# Drive_Board_Schematic_3_motors.net
KiCad netlist of a schematic drawn in Altium Designer
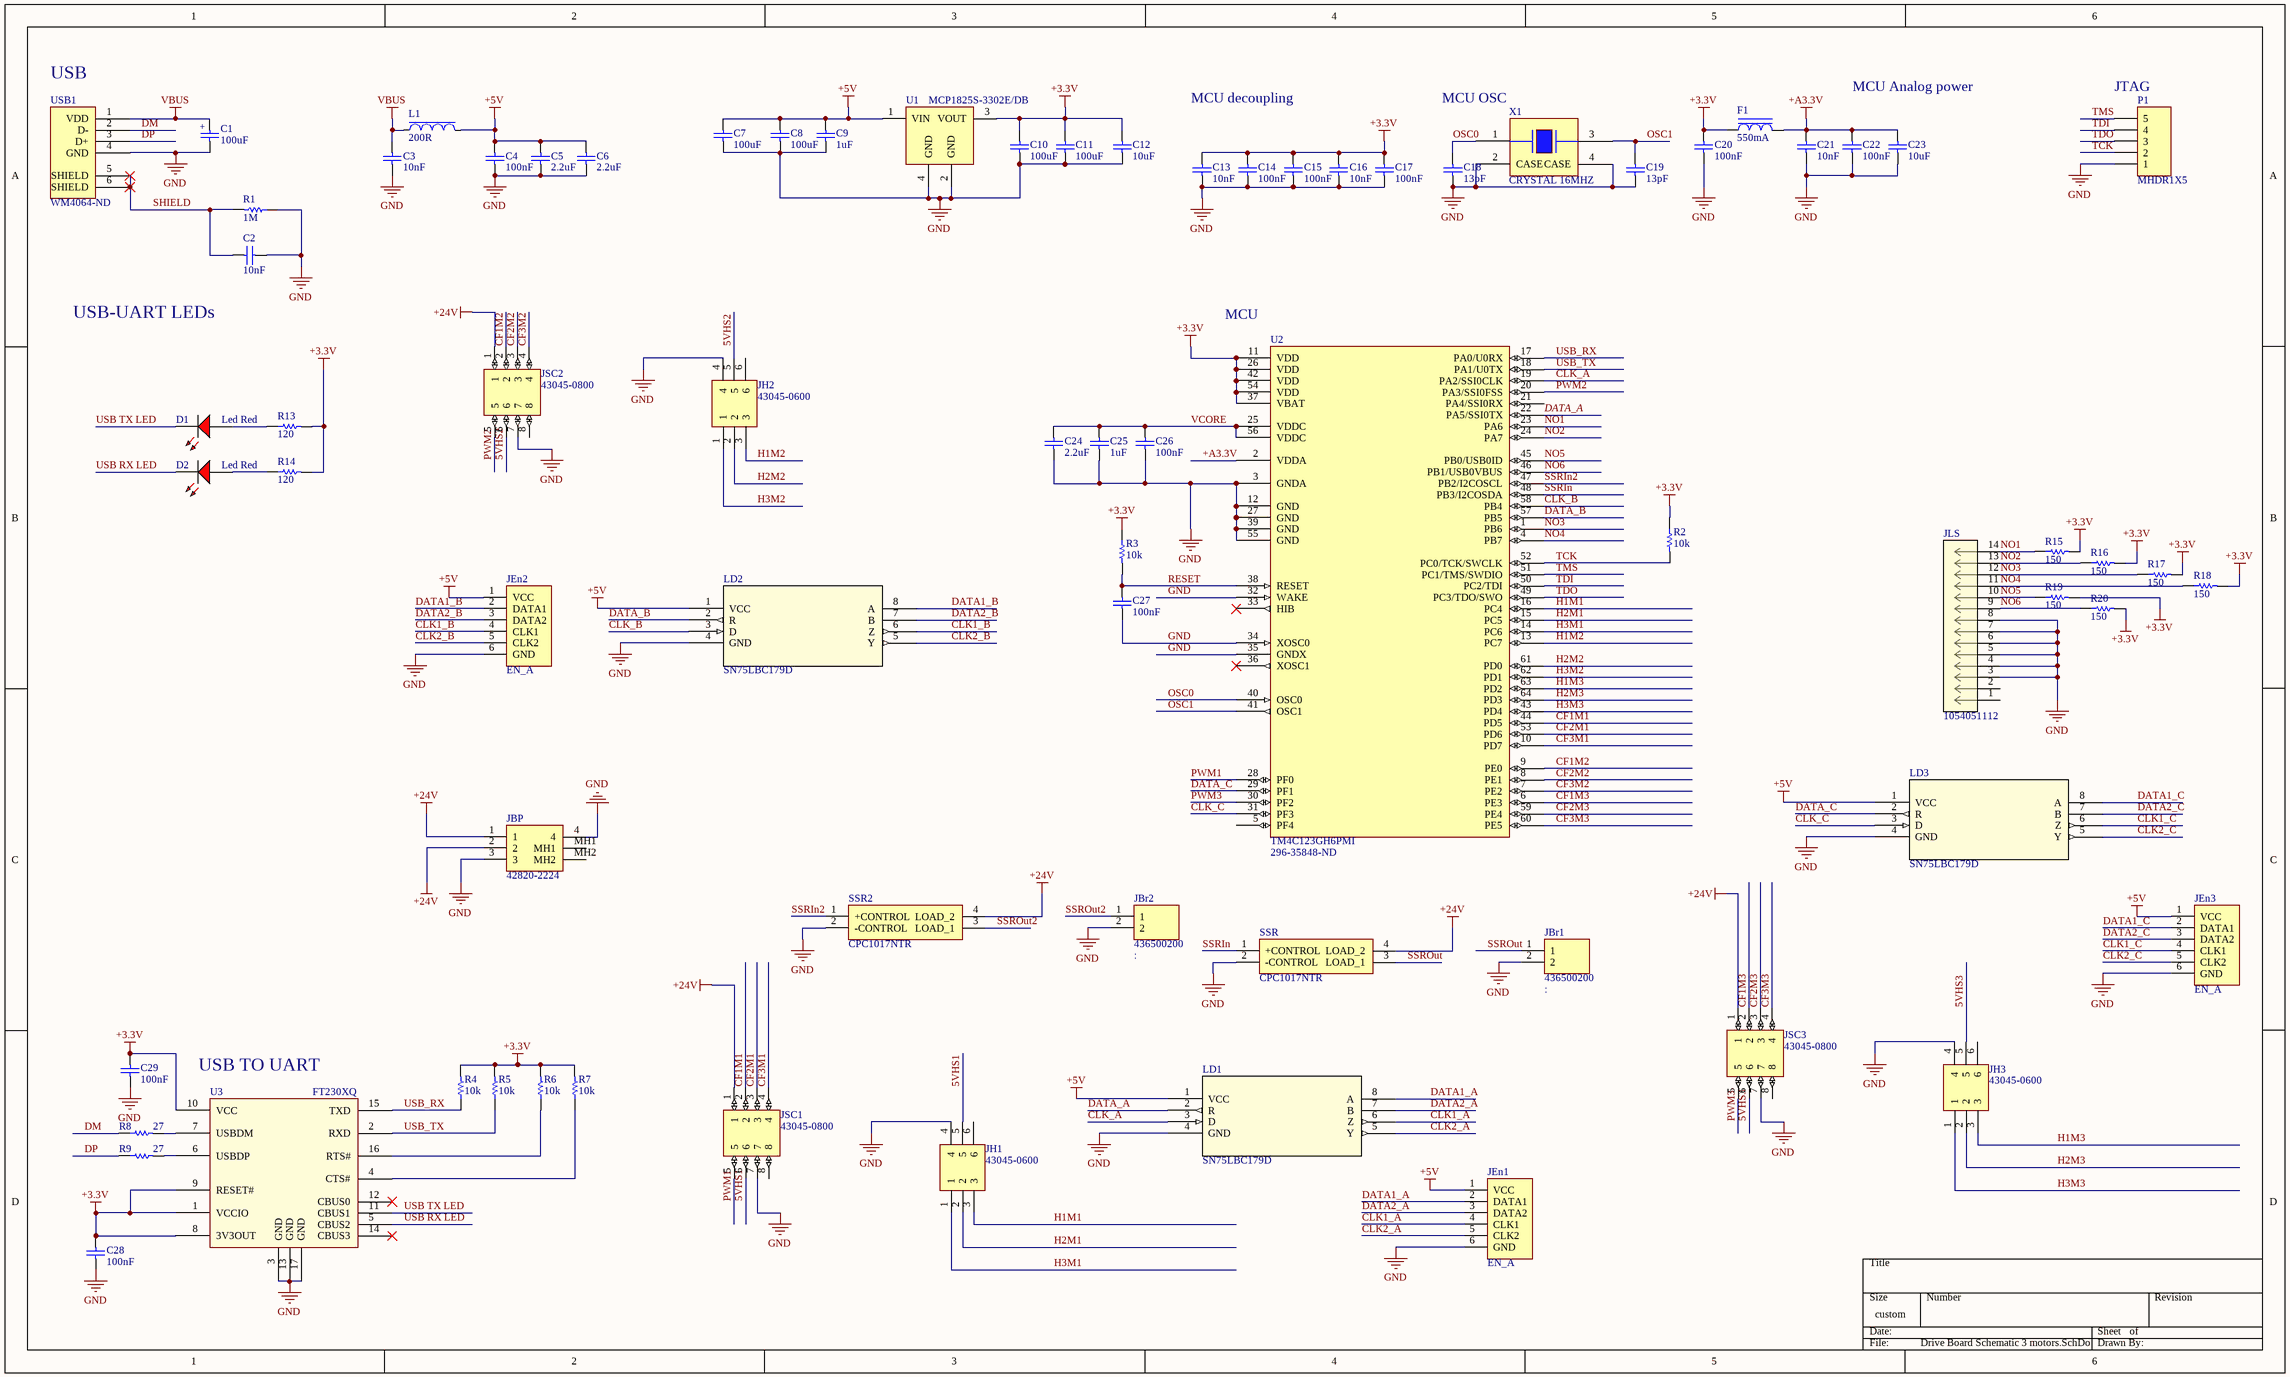
[diagram p0: Drive Board Schematic 3 motors.SchDoc]

(export (version "E")
  (design (tool "Eeschema 10.0.6"))
  (components
    (comp (ref "C1")
      (value "100uF")
      (footprint "CapAlu6.3mmx12.5mm")
      (description "Capacitor 35v 100uF 6.3mm")
      (fields
        (field (name "MANUFACTURER") "Nichicon")
        (field (name "MANUFACTURER PART NUMBER") "UHV1V101MED")
      )
      (libsource (lib "Capacitors") (part "100uF_35v_6.3x12.5"))
    )
    (comp (ref "C2")
      (value "10nF")
      (footprint "CAP_1206")
      (description "CAP CER 10000PF 500V X7R 1206")
      (fields
        (field (name "MANUFACTURER") "Samsung Electro-Mechanics America, Inc")
        (field (name "MANUFACTURER PART NUMBER") "CL31B103KGFNNNE")
      )
      (libsource (lib "Capacitors") (part "10nF_500V_1206"))
    )
    (comp (ref "C3")
      (value "10nF")
      (footprint "CAP_0402_M")
      (description "CAP CER 10000PF 50V 10% X7R 0402")
      (fields
        (field (name "MANUFACTURER") "Kemet")
        (field (name "MANUFACTURER PART NUMBER") "C0402C103K5RACTU")
      )
      (libsource (lib "Capacitors") (part "10nF_50V_0402"))
    )
    (comp (ref "C4")
      (value "100nF")
      (footprint "CAP_0402_M")
      (description "CAP CER 100NF 50V 20% X5R 0402")
      (fields
        (field (name "MANUFACTURER") "TDK Corporation")
        (field (name "MANUFACTURER PART NUMBER") "C1005X5R1H104M050BB")
      )
      (libsource (lib "Capacitors") (part "100nF_50V_0402"))
    )
    (comp (ref "C5")
      (value "2.2uF")
      (footprint "CAP_0402_M")
      (description "CAP CER 2.2UF 10V 20% X5R 0402")
      (fields
        (field (name "MANUFACTURER") "Taiyo Yuden")
        (field (name "MANUFACTURER PART NUMBER") "LMK105BJ225MV-F")
      )
      (libsource (lib "Capacitors") (part "2.2uF_10V_0402"))
    )
    (comp (ref "C6")
      (value "2.2uF")
      (footprint "CAP_0402_M")
      (description "CAP CER 2.2UF 10V 20% X5R 0402")
      (fields
        (field (name "MANUFACTURER") "Taiyo Yuden")
        (field (name "MANUFACTURER PART NUMBER") "LMK105BJ225MV-F")
      )
      (libsource (lib "Capacitors") (part "2.2uF_10V_0402"))
    )
    (comp (ref "C7")
      (value "100uF")
      (footprint "CAP_1206")
      (description "CAP CER 100UF 6.3V X5R 1206")
      (fields
        (field (name "MANUFACTURER") "Murata Electronics North America")
        (field (name "MANUFACTURER PART NUMBER") "GRM31CR60J107ME39L")
      )
      (libsource (lib "Capacitors") (part "100uF_6.3v_1206_X5R"))
    )
    (comp (ref "C8")
      (value "100uF")
      (footprint "CAP_1206")
      (description "CAP CER 100UF 6.3V X5R 1206")
      (fields
        (field (name "MANUFACTURER") "Murata Electronics North America")
        (field (name "MANUFACTURER PART NUMBER") "GRM31CR60J107ME39L")
      )
      (libsource (lib "Capacitors") (part "100uF_6.3v_1206_X5R"))
    )
    (comp (ref "C9")
      (value "1uF")
      (footprint "CAP_0402_M")
      (description "CAP CER 1UF 25V 10% X5R 0402")
      (fields
        (field (name "MANUFACTURER") "TDK Corporation")
        (field (name "MANUFACTURER PART NUMBER") "C1005X5R1E105K050BC")
      )
      (libsource (lib "Capacitors") (part "1uF_25V_0402"))
    )
    (comp (ref "C10")
      (value "100uF")
      (footprint "CAP_1206")
      (description "CAP CER 100UF 6.3V X5R 1206")
      (fields
        (field (name "MANUFACTURER") "Murata Electronics North America")
        (field (name "MANUFACTURER PART NUMBER") "GRM31CR60J107ME39L")
      )
      (libsource (lib "Capacitors") (part "100uF_6.3v_1206_X5R"))
    )
    (comp (ref "C11")
      (value "100uF")
      (footprint "CAP_1206")
      (description "CAP CER 100UF 6.3V X5R 1206")
      (fields
        (field (name "MANUFACTURER") "Murata Electronics North America")
        (field (name "MANUFACTURER PART NUMBER") "GRM31CR60J107ME39L")
      )
      (libsource (lib "Capacitors") (part "100uF_6.3v_1206_X5R"))
    )
    (comp (ref "C12")
      (value "10uF")
      (footprint "CAP_0603")
      (description "CAP CER 10UF 10V 20% X5R 0603")
      (fields
        (field (name "MANUFACTURER") "Taiyo Yuden")
        (field (name "MANUFACTURER PART NUMBER") "LMK107BBJ106MAHT")
      )
      (libsource (lib "Capacitors") (part "10uF_10V_0603"))
    )
    (comp (ref "C13")
      (value "10nF")
      (footprint "CAP_0402_M")
      (description "CAP CER 10000PF 50V 10% X7R 0402")
      (fields
        (field (name "MANUFACTURER") "Kemet")
        (field (name "MANUFACTURER PART NUMBER") "C0402C103K5RACTU")
      )
      (libsource (lib "Capacitors") (part "10nF_50V_0402"))
    )
    (comp (ref "C14")
      (value "100nF")
      (footprint "CAP_0402_M")
      (description "CAP CER 100NF 50V 20% X5R 0402")
      (fields
        (field (name "MANUFACTURER") "TDK Corporation")
        (field (name "MANUFACTURER PART NUMBER") "C1005X5R1H104M050BB")
      )
      (libsource (lib "Capacitors") (part "100nF_50V_0402"))
    )
    (comp (ref "C15")
      (value "100nF")
      (footprint "CAP_0402_M")
      (description "CAP CER 100NF 50V 20% X5R 0402")
      (fields
        (field (name "MANUFACTURER") "TDK Corporation")
        (field (name "MANUFACTURER PART NUMBER") "C1005X5R1H104M050BB")
      )
      (libsource (lib "Capacitors") (part "100nF_50V_0402"))
    )
    (comp (ref "C16")
      (value "10nF")
      (footprint "CAP_0402_M")
      (description "CAP CER 10000PF 50V 10% X7R 0402")
      (fields
        (field (name "MANUFACTURER") "Kemet")
        (field (name "MANUFACTURER PART NUMBER") "C0402C103K5RACTU")
      )
      (libsource (lib "Capacitors") (part "10nF_50V_0402"))
    )
    (comp (ref "C17")
      (value "100nF")
      (footprint "CAP_0402_M")
      (description "CAP CER 100NF 50V 20% X5R 0402")
      (fields
        (field (name "MANUFACTURER") "TDK Corporation")
        (field (name "MANUFACTURER PART NUMBER") "C1005X5R1H104M050BB")
      )
      (libsource (lib "Capacitors") (part "100nF_50V_0402"))
    )
    (comp (ref "C18")
      (value "13pF")
      (footprint "CAP_0402_M")
      (description "CAP CER 13PF 50V 5% NP0 0402")
      (fields
        (field (name "MANUFACTURER") "Samsung Electro-Mechanics America, Inc")
        (field (name "MANUFACTURER PART NUMBER") "CL05C130JB5NNNC")
      )
      (libsource (lib "Capacitors") (part "13pF_50V_0402"))
    )
    (comp (ref "C19")
      (value "13pF")
      (footprint "CAP_0402_M")
      (description "CAP CER 13PF 50V 5% NP0 0402")
      (fields
        (field (name "MANUFACTURER") "Samsung Electro-Mechanics America, Inc")
        (field (name "MANUFACTURER PART NUMBER") "CL05C130JB5NNNC")
      )
      (libsource (lib "Capacitors") (part "13pF_50V_0402"))
    )
    (comp (ref "C20")
      (value "100nF")
      (footprint "CAP_0402_M")
      (description "CAP CER 100NF 50V 20% X5R 0402")
      (fields
        (field (name "MANUFACTURER") "TDK Corporation")
        (field (name "MANUFACTURER PART NUMBER") "C1005X5R1H104M050BB")
      )
      (libsource (lib "Capacitors") (part "100nF_50V_0402"))
    )
    (comp (ref "C21")
      (value "10nF")
      (footprint "CAP_0402_M")
      (description "CAP CER 10000PF 50V 10% X7R 0402")
      (fields
        (field (name "MANUFACTURER") "Kemet")
        (field (name "MANUFACTURER PART NUMBER") "C0402C103K5RACTU")
      )
      (libsource (lib "Capacitors") (part "10nF_50V_0402"))
    )
    (comp (ref "C22")
      (value "100nF")
      (footprint "CAP_0402_M")
      (description "CAP CER 100NF 50V 20% X5R 0402")
      (fields
        (field (name "MANUFACTURER") "TDK Corporation")
        (field (name "MANUFACTURER PART NUMBER") "C1005X5R1H104M050BB")
      )
      (libsource (lib "Capacitors") (part "100nF_50V_0402"))
    )
    (comp (ref "C23")
      (value "10uF")
      (footprint "CAP_0603")
      (description "CAP CER 10UF 10V 20% X5R 0603")
      (fields
        (field (name "MANUFACTURER") "Taiyo Yuden")
        (field (name "MANUFACTURER PART NUMBER") "LMK107BBJ106MAHT")
      )
      (libsource (lib "Capacitors") (part "10uF_10V_0603"))
    )
    (comp (ref "C24")
      (value "2.2uF")
      (footprint "CAP_0603")
      (description "CAP CER 2.2UF 35V 10% X5R 0603")
      (fields
        (field (name "MANUFACTURER") "Murata Electronics North America")
        (field (name "MANUFACTURER PART NUMBER") "GRM188R6YA225KA12D")
      )
      (libsource (lib "Capacitors") (part "2.2uF_35V_0603"))
    )
    (comp (ref "C25")
      (value "1uF")
      (footprint "CAP_0402_M")
      (description "CAP CER 1UF 25V 10% X5R 0402")
      (fields
        (field (name "MANUFACTURER") "TDK Corporation")
        (field (name "MANUFACTURER PART NUMBER") "C1005X5R1E105K050BC")
      )
      (libsource (lib "Capacitors") (part "1uF_25V_0402"))
    )
    (comp (ref "C26")
      (value "100nF")
      (footprint "CAP_0402_M")
      (description "CAP CER 100NF 50V 20% X5R 0402")
      (fields
        (field (name "MANUFACTURER") "TDK Corporation")
        (field (name "MANUFACTURER PART NUMBER") "C1005X5R1H104M050BB")
      )
      (libsource (lib "Capacitors") (part "100nF_50V_0402"))
    )
    (comp (ref "C27")
      (value "100nF")
      (footprint "CAP_0402_M")
      (description "CAP CER 100NF 50V 20% X5R 0402")
      (fields
        (field (name "MANUFACTURER") "TDK Corporation")
        (field (name "MANUFACTURER PART NUMBER") "C1005X5R1H104M050BB")
      )
      (libsource (lib "Capacitors") (part "100nF_50V_0402"))
    )
    (comp (ref "C28")
      (value "100nF")
      (footprint "CAP_0402_M")
      (description "CAP CER 100NF 50V 20% X5R 0402")
      (fields
        (field (name "MANUFACTURER") "TDK Corporation")
        (field (name "MANUFACTURER PART NUMBER") "C1005X5R1H104M050BB")
      )
      (libsource (lib "Capacitors") (part "100nF_50V_0402"))
    )
    (comp (ref "C29")
      (value "100nF")
      (footprint "CAP_0402_M")
      (description "CAP CER 100NF 50V 20% X5R 0402")
      (fields
        (field (name "MANUFACTURER") "TDK Corporation")
        (field (name "MANUFACTURER PART NUMBER") "C1005X5R1H104M050BB")
      )
      (libsource (lib "Capacitors") (part "100nF_50V_0402"))
    )
    (comp (ref "D1")
      (value "Led Red")
      (footprint "TOPLED 0805")
      (description "LED TOPLED 630NM SUP RED CLR SMD")
      (fields
        (field (name "MANUFACTURER") "OSRAM Opto Semiconductors Inc")
        (field (name "MANUFACTURER PART NUMBER") "LS M67K-H2L1-1-Z")
      )
      (libsource (lib "Diodes") (part "TOPLED 0803"))
    )
    (comp (ref "D2")
      (value "Led Red")
      (footprint "TOPLED 0805")
      (description "LED TOPLED 630NM SUP RED CLR SMD")
      (fields
        (field (name "MANUFACTURER") "OSRAM Opto Semiconductors Inc")
        (field (name "MANUFACTURER PART NUMBER") "LS M67K-H2L1-1-Z")
      )
      (libsource (lib "Diodes") (part "TOPLED 0803"))
    )
    (comp (ref "F1")
      (value "550mA")
      (footprint "RES_0402_M")
      (description "FERRITE CHIP 40 OHM 550MA 0402")
      (fields
        (field (name "MANUFACTURER") "TDK Corporation")
        (field (name "MANUFACTURER PART NUMBER") "MMZ1005Y400CT000")
      )
      (libsource (lib "Resistors") (part "40O_550mA_0402"))
    )
    (comp (ref "JBP")
      (value "42820-2224")
      (footprint "SamacSys:428202224")
      (description "Connector")
      (fields (field (name "MOUSER PART NUMBER") "538-42820-2224"))
      (libsource (lib "*") (part "42820-2224"))
    )
    (comp (ref "JBr1")
      (value "436500200")
      (footprint "MOLEX_436500200")
      (description "Connector Header Through Hole, Right Angle 2 position 0.118 (3.00mm)")
      (fields (field (name "MF") "Molex"))
      (libsource (lib "436500200") (part "436500200"))
    )
    (comp (ref "JBr2")
      (value "436500200")
      (footprint "MOLEX_436500200")
      (description "Connector Header Through Hole, Right Angle 2 position 0.118 (3.00mm)")
      (fields (field (name "MF") "Molex"))
      (libsource (lib "436500200") (part "436500200"))
    )
    (comp (ref "JEn1")
      (value "EN_A")
      (footprint "SamacSys:1053091106")
      (description "Connector")
      (fields (field (name "MANUFACTURER_PART_NUMBER") "105309-1106"))
      (libsource (lib "*") (part "105309-1106"))
    )
    (comp (ref "JEn2")
      (value "EN_A")
      (footprint "SamacSys:1053091106")
      (description "Connector")
      (fields (field (name "MANUFACTURER_PART_NUMBER") "105309-1106"))
      (libsource (lib "*") (part "105309-1106"))
    )
    (comp (ref "JEn3")
      (value "EN_A")
      (footprint "SamacSys:1053091106")
      (description "Connector")
      (fields (field (name "MANUFACTURER_PART_NUMBER") "105309-1106"))
      (libsource (lib "*") (part "105309-1106"))
    )
    (comp (ref "JH1")
      (value "43045-0600")
      (footprint "SamacSys:43045-0600")
      (description "Connector")
      (fields (field (name "MOUSER PART NUMBER") "538-43045-0600"))
      (libsource (lib "*") (part "43045-0600"))
    )
    (comp (ref "JH2")
      (value "43045-0600")
      (footprint "SamacSys:43045-0600")
      (description "Connector")
      (fields (field (name "MOUSER PART NUMBER") "538-43045-0600"))
      (libsource (lib "*") (part "43045-0600"))
    )
    (comp (ref "JH3")
      (value "43045-0600")
      (footprint "SamacSys:43045-0600")
      (description "Connector")
      (fields (field (name "MOUSER PART NUMBER") "538-43045-0600"))
      (libsource (lib "*") (part "43045-0600"))
    )
    (comp (ref "JLS")
      (value "1054051112")
      (footprint "CON_1054051112_MOL")
      (description "No Description Available")
      (fields (field (name "COPYRIGHT") "Copyright (C) 2018 Accelerated Designs. All rights reserved"))
      (libsource (lib "Molex 1054051112") (part "1054051112"))
    )
    (comp (ref "JSC1")
      (value "43045-0800")
      (footprint "43045-0800")
      (description "Connector")
      (fields (field (name "MOUSER PART NUMBER") "538-43045-0800"))
      (libsource (lib "SamacSys") (part "43045-0800"))
    )
    (comp (ref "JSC2")
      (value "43045-0800")
      (footprint "43045-0800")
      (description "Connector")
      (fields (field (name "MOUSER PART NUMBER") "538-43045-0800"))
      (libsource (lib "SamacSys") (part "43045-0800"))
    )
    (comp (ref "JSC3")
      (value "43045-0800")
      (footprint "43045-0800")
      (description "Connector")
      (fields (field (name "MOUSER PART NUMBER") "538-43045-0800"))
      (libsource (lib "SamacSys") (part "43045-0800"))
    )
    (comp (ref "L1")
      (value "200R")
      (footprint "IND_0603")
      (description "FILTER CHIP 220 OHM 2A 0603")
      (fields
        (field (name "MANUFACTURER") "Murata Electronics North America")
        (field (name "MANUFACTURER PART NUMBER") "BLM18EG221SN1D")
      )
      (libsource (lib "Inductors") (part "Ferrite_200 ohms_2A"))
    )
    (comp (ref "LD1")
      (value "SN75LBC179D")
      (footprint "D8")
      (description "Low-Power Differential Line Driver And Receiver Pair")
      (fields
        (field (name "MANUFACTURER") "Texas Instruments")
        (field (name "GENERIC_PART_NUMBER") "SN75LBC179")
        (field (name "COPYRIGHT") "Copyright (C) 2018 Accelerated Designs. All rights reserved")
      )
      (libsource (lib "2020-08-25_19-06-54") (part "SN75LBC179D"))
    )
    (comp (ref "LD2")
      (value "SN75LBC179D")
      (footprint "D8")
      (description "Low-Power Differential Line Driver And Receiver Pair")
      (fields
        (field (name "MANUFACTURER") "Texas Instruments")
        (field (name "GENERIC_PART_NUMBER") "SN75LBC179")
        (field (name "COPYRIGHT") "Copyright (C) 2018 Accelerated Designs. All rights reserved")
      )
      (libsource (lib "2020-08-25_19-06-54") (part "SN75LBC179D"))
    )
    (comp (ref "LD3")
      (value "SN75LBC179D")
      (footprint "D8")
      (description "Low-Power Differential Line Driver And Receiver Pair")
      (fields
        (field (name "MANUFACTURER") "Texas Instruments")
        (field (name "GENERIC_PART_NUMBER") "SN75LBC179")
        (field (name "COPYRIGHT") "Copyright (C) 2018 Accelerated Designs. All rights reserved")
      )
      (libsource (lib "2020-08-25_19-06-54") (part "SN75LBC179D"))
    )
    (comp (ref "P1")
      (value "MHDR1X5")
      (footprint "MHDR1X5")
      (description "Header, 5-Pin")
      (fields (field (name "PUBLISHER") "Altium Limited"))
      (libsource (lib "Miscellaneous Connectors") (part "MHDR1X5"))
    )
    (comp (ref "R1")
      (value "1M")
      (footprint "RES_1206")
      (description "RES SMD 1M OHM 5% 1/4W 1206")
      (fields
        (field (name "MANUFACTURER") "Panasonic Electronic Components")
        (field (name "MANUFACTURER PART NUMBER") "ERJ-8GEYJ105V")
      )
      (libsource (lib "Resistors") (part "1M_5%_1206"))
    )
    (comp (ref "R2")
      (value "10k")
      (footprint "RES_0402_M")
      (description "RES SMD 10K OHM 1% 1/10W 0402")
      (fields
        (field (name "MANUFACTURER") "Panasonic Electronic Components")
        (field (name "MANUFACTURER PART NUMBER") "ERJ-2RKF1002X")
      )
      (libsource (lib "Resistors") (part "10k_1%_0402"))
    )
    (comp (ref "R3")
      (value "10k")
      (footprint "RES_0402_M")
      (description "RES SMD 10K OHM 1% 1/10W 0402")
      (fields
        (field (name "MANUFACTURER") "Panasonic Electronic Components")
        (field (name "MANUFACTURER PART NUMBER") "ERJ-2RKF1002X")
      )
      (libsource (lib "Resistors") (part "10k_1%_0402"))
    )
    (comp (ref "R4")
      (value "10k")
      (footprint "RES_0402_M")
      (description "RES SMD 10K OHM 1% 1/10W 0402")
      (fields
        (field (name "MANUFACTURER") "Panasonic Electronic Components")
        (field (name "MANUFACTURER PART NUMBER") "ERJ-2RKF1002X")
      )
      (libsource (lib "Resistors") (part "10k_1%_0402"))
    )
    (comp (ref "R5")
      (value "10k")
      (footprint "RES_0402_M")
      (description "RES SMD 10K OHM 1% 1/10W 0402")
      (fields
        (field (name "MANUFACTURER") "Panasonic Electronic Components")
        (field (name "MANUFACTURER PART NUMBER") "ERJ-2RKF1002X")
      )
      (libsource (lib "Resistors") (part "10k_1%_0402"))
    )
    (comp (ref "R6")
      (value "10k")
      (footprint "RES_0402_M")
      (description "RES SMD 10K OHM 1% 1/10W 0402")
      (fields
        (field (name "MANUFACTURER") "Panasonic Electronic Components")
        (field (name "MANUFACTURER PART NUMBER") "ERJ-2RKF1002X")
      )
      (libsource (lib "Resistors") (part "10k_1%_0402"))
    )
    (comp (ref "R7")
      (value "10k")
      (footprint "RES_0402_M")
      (description "RES SMD 10K OHM 1% 1/10W 0402")
      (fields
        (field (name "MANUFACTURER") "Panasonic Electronic Components")
        (field (name "MANUFACTURER PART NUMBER") "ERJ-2RKF1002X")
      )
      (libsource (lib "Resistors") (part "10k_1%_0402"))
    )
    (comp (ref "R8")
      (value "27")
      (footprint "RES_0402_M")
      (description "RES SMD 27 OHM 1% 1/10W 0402")
      (fields
        (field (name "MANUFACTURER") "Panasonic Electronic Components")
        (field (name "MANUFACTURER PART NUMBER") "ERJ-2RKF27R0X")
      )
      (libsource (lib "Resistors") (part "27_1%_0402"))
    )
    (comp (ref "R9")
      (value "27")
      (footprint "RES_0402_M")
      (description "RES SMD 27 OHM 1% 1/10W 0402")
      (fields
        (field (name "MANUFACTURER") "Panasonic Electronic Components")
        (field (name "MANUFACTURER PART NUMBER") "ERJ-2RKF27R0X")
      )
      (libsource (lib "Resistors") (part "27_1%_0402"))
    )
    (comp (ref "R13")
      (value "120")
      (footprint "RES_0402_M")
      (description "RES SMD 120 OHM 1% 1/10W 0402")
      (fields
        (field (name "MANUFACTURER") "Panasonic Electronic Components")
        (field (name "MANUFACTURER PART NUMBER") "ERJ-2RKF1200X")
      )
      (libsource (lib "Resistors") (part "120_1%_0402"))
    )
    (comp (ref "R14")
      (value "120")
      (footprint "RES_0402_M")
      (description "RES SMD 120 OHM 1% 1/10W 0402")
      (fields
        (field (name "MANUFACTURER") "Panasonic Electronic Components")
        (field (name "MANUFACTURER PART NUMBER") "ERJ-2RKF1200X")
      )
      (libsource (lib "Resistors") (part "120_1%_0402"))
    )
    (comp (ref "R15")
      (value "150")
      (footprint "RES_0402_M")
      (description "RES SMD 10K OHM 1% 1/10W 0402")
      (fields
        (field (name "MANUFACTURER") "Panasonic Electronic Components")
        (field (name "MANUFACTURER PART NUMBER") "ERJ-2RKF1002X")
      )
      (libsource (lib "Resistors") (part "10k_1%_0402"))
    )
    (comp (ref "R16")
      (value "150")
      (footprint "RES_0402_M")
      (description "RES SMD 10K OHM 1% 1/10W 0402")
      (fields
        (field (name "MANUFACTURER") "Panasonic Electronic Components")
        (field (name "MANUFACTURER PART NUMBER") "ERJ-2RKF1002X")
      )
      (libsource (lib "Resistors") (part "10k_1%_0402"))
    )
    (comp (ref "R17")
      (value "150")
      (footprint "RES_0402_M")
      (description "RES SMD 10K OHM 1% 1/10W 0402")
      (fields
        (field (name "MANUFACTURER") "Panasonic Electronic Components")
        (field (name "MANUFACTURER PART NUMBER") "ERJ-2RKF1002X")
      )
      (libsource (lib "Resistors") (part "10k_1%_0402"))
    )
    (comp (ref "R18")
      (value "150")
      (footprint "RES_0402_M")
      (description "RES SMD 10K OHM 1% 1/10W 0402")
      (fields
        (field (name "MANUFACTURER") "Panasonic Electronic Components")
        (field (name "MANUFACTURER PART NUMBER") "ERJ-2RKF1002X")
      )
      (libsource (lib "Resistors") (part "10k_1%_0402"))
    )
    (comp (ref "R19")
      (value "150")
      (footprint "RES_0402_M")
      (description "RES SMD 10K OHM 1% 1/10W 0402")
      (fields
        (field (name "MANUFACTURER") "Panasonic Electronic Components")
        (field (name "MANUFACTURER PART NUMBER") "ERJ-2RKF1002X")
      )
      (libsource (lib "Resistors") (part "10k_1%_0402"))
    )
    (comp (ref "R20")
      (value "150")
      (footprint "RES_0402_M")
      (description "RES SMD 10K OHM 1% 1/10W 0402")
      (fields
        (field (name "MANUFACTURER") "Panasonic Electronic Components")
        (field (name "MANUFACTURER PART NUMBER") "ERJ-2RKF1002X")
      )
      (libsource (lib "Resistors") (part "10k_1%_0402"))
    )
    (comp (ref "SSR")
      (value "CPC1017NTR")
      (footprint "SamacSys:SOP254P610X216-4N")
      (description "Relay or Contactor")
      (fields (field (name "MOUSER PART NUMBER") "849-CPC1017NTR"))
      (libsource (lib "*") (part "CPC1017NTR"))
    )
    (comp (ref "SSR2")
      (value "CPC1017NTR")
      (footprint "SamacSys:SOP254P610X216-4N")
      (description "Relay or Contactor")
      (fields (field (name "MOUSER PART NUMBER") "849-CPC1017NTR"))
      (libsource (lib "*") (part "CPC1017NTR"))
    )
    (comp (ref "U1")
      (value "MCP1825S-3302E/DB")
      (footprint "SOT230P700X180-4N")
      (description "500 mA, Low Voltage, Low Quiescent Current LDO Regulator")
      (fields (field (name "MANUFACTURER") "Microchip Technology"))
      (libsource (lib "ICs") (part "MCP1825S-3302E/DB"))
    )
    (comp (ref "U2")
      (value "TM4C123GH6PMI")
      (footprint "TSQFP50P1200X1200X120-64N")
      (description "Tiva TM4C123GH6PM Microcontroller ARM Cortex 80 MHz FPU")
      (fields (field (name "SUPPLIER PART NUMBER 1") "296-35848-ND"))
      (libsource (lib "ICs") (part "TM4C123GH6PMI"))
    )
    (comp (ref "U3")
      (value "FT230XQ")
      (footprint "QFN65P400X400X80_HS-17N")
      (description "IC USB SERIAL BASIC UART 16QFN")
      (fields
        (field (name "MANUFACTURER") "FTDI, Future Technology Devices International Ltd")
        (field (name "MANUFACTURER PART NUMBER") "FT230XQ-R")
      )
      (libsource (lib "ICs") (part "FT230XQ-R"))
    )
    (comp (ref "USB1")
      (value "USB type-B jack")
      (footprint "USB2.5-2H4E")
      (fields (field (name "SUPPLIER PART NUMBER 1") "WM4064-ND"))
      (libsource (lib "Connectors") (part "MOLEX 0670688010"))
    )
    (comp (ref "X1")
      (value "CRYSTAL 16MHZ")
      (footprint "CRYSTAL_3.2x2.5")
      (description "CRYSTAL 16MHZ 20PF SMD")
      (fields
        (field (name "MANUFACTURER") "CTS-Frequency Controls")
        (field (name "MANUFACTURER PART NUMBER") "403C35E16M00000")
      )
      (libsource (lib "ICs") (part "403C35E16M00000"))
    )
  )
  (nets
    (net (code "1") (name "+3.3V") (class "Default")
      (node (ref "C10") (pin "1") (pinfunction "1_1") (pintype "passive"))
      (node (ref "C11") (pin "1") (pinfunction "1_1") (pintype "passive"))
      (node (ref "C12") (pin "1") (pinfunction "1_1") (pintype "passive"))
      (node (ref "C13") (pin "2") (pinfunction "2_2") (pintype "passive"))
      (node (ref "C14") (pin "2") (pinfunction "2_2") (pintype "passive"))
      (node (ref "C15") (pin "2") (pinfunction "2_2") (pintype "passive"))
      (node (ref "C16") (pin "2") (pinfunction "2_2") (pintype "passive"))
      (node (ref "C17") (pin "2") (pinfunction "2_2") (pintype "passive"))
      (node (ref "C20") (pin "2") (pinfunction "2_2") (pintype "passive"))
      (node (ref "C28") (pin "2") (pinfunction "2_2") (pintype "passive"))
      (node (ref "C29") (pin "2") (pinfunction "2_2") (pintype "passive"))
      (node (ref "F1") (pin "1") (pinfunction "1_1") (pintype "passive"))
      (node (ref "R13") (pin "2") (pinfunction "2_2") (pintype "passive"))
      (node (ref "R14") (pin "2") (pinfunction "2_2") (pintype "passive"))
      (node (ref "R15") (pin "2") (pinfunction "2_2") (pintype "passive"))
      (node (ref "R16") (pin "2") (pinfunction "2_2") (pintype "passive"))
      (node (ref "R17") (pin "2") (pinfunction "2_2") (pintype "passive"))
      (node (ref "R18") (pin "2") (pinfunction "2_2") (pintype "passive"))
      (node (ref "R19") (pin "2") (pinfunction "2_2") (pintype "passive"))
      (node (ref "R2") (pin "1") (pinfunction "1_1") (pintype "passive"))
      (node (ref "R20") (pin "2") (pinfunction "2_2") (pintype "passive"))
      (node (ref "R3") (pin "1") (pinfunction "1_1") (pintype "passive"))
      (node (ref "R4") (pin "2") (pinfunction "2_2") (pintype "passive"))
      (node (ref "R5") (pin "2") (pinfunction "2_2") (pintype "passive"))
      (node (ref "R6") (pin "2") (pinfunction "2_2") (pintype "passive"))
      (node (ref "R7") (pin "2") (pinfunction "2_2") (pintype "passive"))
      (node (ref "U1") (pin "3") (pinfunction "VOUT_3") (pintype "power_in"))
      (node (ref "U2") (pin "11") (pinfunction "VDD_11") (pintype "power_in"))
      (node (ref "U2") (pin "26") (pinfunction "VDD_26") (pintype "power_in"))
      (node (ref "U2") (pin "37") (pinfunction "VBAT_37") (pintype "power_in"))
      (node (ref "U2") (pin "42") (pinfunction "VDD_42") (pintype "power_in"))
      (node (ref "U2") (pin "54") (pinfunction "VDD_54") (pintype "power_in"))
      (node (ref "U3") (pin "1") (pinfunction "VCCIO_1") (pintype "passive"))
      (node (ref "U3") (pin "10") (pinfunction "VCC_10") (pintype "passive"))
      (node (ref "U3") (pin "8") (pinfunction "3V3OUT_8") (pintype "passive"))
      (node (ref "U3") (pin "9") (pinfunction "RESET#_9") (pintype "passive"))
    )
    (net (code "2") (name "+5V") (class "Default")
      (node (ref "C4") (pin "2") (pinfunction "2_2") (pintype "passive"))
      (node (ref "C5") (pin "2") (pinfunction "2_2") (pintype "passive"))
      (node (ref "C6") (pin "2") (pinfunction "2_2") (pintype "passive"))
      (node (ref "C7") (pin "1") (pinfunction "1_1") (pintype "passive"))
      (node (ref "C8") (pin "1") (pinfunction "1_1") (pintype "passive"))
      (node (ref "C9") (pin "2") (pinfunction "2_2") (pintype "passive"))
      (node (ref "JEn1") (pin "1") (pinfunction "VCC_1") (pintype "passive"))
      (node (ref "JEn2") (pin "1") (pinfunction "VCC_1") (pintype "passive"))
      (node (ref "JEn3") (pin "1") (pinfunction "VCC_1") (pintype "passive"))
      (node (ref "L1") (pin "2") (pinfunction "2_2") (pintype "passive"))
      (node (ref "LD1") (pin "1") (pinfunction "VCC_1") (pintype "power_in"))
      (node (ref "LD2") (pin "1") (pinfunction "VCC_1") (pintype "power_in"))
      (node (ref "LD3") (pin "1") (pinfunction "VCC_1") (pintype "power_in"))
      (node (ref "U1") (pin "1") (pinfunction "VIN_1") (pintype "power_in"))
    )
    (net (code "3") (name "+24V") (class "Default")
      (node (ref "JBP") (pin "1") (pinfunction "1_1") (pintype "passive"))
      (node (ref "JBP") (pin "2") (pinfunction "2_2") (pintype "passive"))
      (node (ref "JSC1") (pin "1") (pinfunction "1_1") (pintype "bidirectional"))
      (node (ref "JSC2") (pin "1") (pinfunction "1_1") (pintype "bidirectional"))
      (node (ref "JSC3") (pin "1") (pinfunction "1_1") (pintype "bidirectional"))
      (node (ref "SSR") (pin "4") (pinfunction "LOAD_2_4") (pintype "passive"))
      (node (ref "SSR2") (pin "4") (pinfunction "LOAD_2_4") (pintype "passive"))
    )
    (net (code "4") (name "+A3.3V") (class "Default")
      (node (ref "C21") (pin "2") (pinfunction "2_2") (pintype "passive"))
      (node (ref "C22") (pin "2") (pinfunction "2_2") (pintype "passive"))
      (node (ref "C23") (pin "2") (pinfunction "2_2") (pintype "passive"))
      (node (ref "F1") (pin "2") (pinfunction "2_2") (pintype "passive"))
      (node (ref "U2") (pin "2") (pinfunction "VDDA_2") (pintype "power_in"))
    )
    (net (code "5") (name "/5VHS1") (class "Default")
      (node (ref "JH1") (pin "5") (pinfunction "5_5") (pintype "passive"))
      (node (ref "JSC1") (pin "6") (pinfunction "6_6") (pintype "bidirectional"))
    )
    (net (code "6") (name "/5VHS2") (class "Default")
      (node (ref "JH2") (pin "5") (pinfunction "5_5") (pintype "passive"))
      (node (ref "JSC2") (pin "6") (pinfunction "6_6") (pintype "bidirectional"))
    )
    (net (code "7") (name "/5VHS3") (class "Default")
      (node (ref "JH3") (pin "5") (pinfunction "5_5") (pintype "passive"))
      (node (ref "JSC3") (pin "6") (pinfunction "6_6") (pintype "bidirectional"))
    )
    (net (code "8") (name "/CF1M1") (class "Default")
      (node (ref "JSC1") (pin "2") (pinfunction "2_2") (pintype "bidirectional"))
      (node (ref "U2") (pin "44") (pinfunction "PD5_44") (pintype "bidirectional"))
    )
    (net (code "9") (name "/CF1M2") (class "Default")
      (node (ref "JSC2") (pin "2") (pinfunction "2_2") (pintype "bidirectional"))
      (node (ref "U2") (pin "9") (pinfunction "PE0_9") (pintype "bidirectional"))
    )
    (net (code "10") (name "/CF1M3") (class "Default")
      (node (ref "JSC3") (pin "2") (pinfunction "2_2") (pintype "bidirectional"))
      (node (ref "U2") (pin "6") (pinfunction "PE3_6") (pintype "bidirectional"))
    )
    (net (code "11") (name "/CF2M1") (class "Default")
      (node (ref "JSC1") (pin "3") (pinfunction "3_3") (pintype "bidirectional"))
      (node (ref "U2") (pin "53") (pinfunction "PD6_53") (pintype "bidirectional"))
    )
    (net (code "12") (name "/CF2M2") (class "Default")
      (node (ref "JSC2") (pin "3") (pinfunction "3_3") (pintype "bidirectional"))
      (node (ref "U2") (pin "8") (pinfunction "PE1_8") (pintype "bidirectional"))
    )
    (net (code "13") (name "/CF2M3") (class "Default")
      (node (ref "JSC3") (pin "3") (pinfunction "3_3") (pintype "bidirectional"))
      (node (ref "U2") (pin "59") (pinfunction "PE4_59") (pintype "bidirectional"))
    )
    (net (code "14") (name "/CF3M1") (class "Default")
      (node (ref "JSC1") (pin "4") (pinfunction "4_4") (pintype "bidirectional"))
      (node (ref "U2") (pin "10") (pinfunction "PD7_10") (pintype "bidirectional"))
    )
    (net (code "15") (name "/CF3M2") (class "Default")
      (node (ref "JSC2") (pin "4") (pinfunction "4_4") (pintype "bidirectional"))
      (node (ref "U2") (pin "7") (pinfunction "PE2_7") (pintype "bidirectional"))
    )
    (net (code "16") (name "/CF3M3") (class "Default")
      (node (ref "JSC3") (pin "4") (pinfunction "4_4") (pintype "bidirectional"))
      (node (ref "U2") (pin "60") (pinfunction "PE5_60") (pintype "bidirectional"))
    )
    (net (code "17") (name "/CLK1_A") (class "Default")
      (node (ref "JEn1") (pin "4") (pinfunction "CLK1_4") (pintype "passive"))
      (node (ref "LD1") (pin "6") (pinfunction "Z_6") (pintype "output"))
    )
    (net (code "18") (name "/CLK1_B") (class "Default")
      (node (ref "JEn2") (pin "4") (pinfunction "CLK1_4") (pintype "passive"))
      (node (ref "LD2") (pin "6") (pinfunction "Z_6") (pintype "output"))
    )
    (net (code "19") (name "/CLK1_C") (class "Default")
      (node (ref "JEn3") (pin "4") (pinfunction "CLK1_4") (pintype "passive"))
      (node (ref "LD3") (pin "6") (pinfunction "Z_6") (pintype "output"))
    )
    (net (code "20") (name "/CLK2_A") (class "Default")
      (node (ref "JEn1") (pin "5") (pinfunction "CLK2_5") (pintype "passive"))
      (node (ref "LD1") (pin "5") (pinfunction "Y_5") (pintype "output"))
    )
    (net (code "21") (name "/CLK2_B") (class "Default")
      (node (ref "JEn2") (pin "5") (pinfunction "CLK2_5") (pintype "passive"))
      (node (ref "LD2") (pin "5") (pinfunction "Y_5") (pintype "output"))
    )
    (net (code "22") (name "/CLK2_C") (class "Default")
      (node (ref "JEn3") (pin "5") (pinfunction "CLK2_5") (pintype "passive"))
      (node (ref "LD3") (pin "5") (pinfunction "Y_5") (pintype "output"))
    )
    (net (code "23") (name "/CLK_A") (class "Default")
      (node (ref "LD1") (pin "3") (pinfunction "D_3") (pintype "input"))
      (node (ref "U2") (pin "19") (pinfunction "PA2/SSI0CLK_19") (pintype "bidirectional"))
    )
    (net (code "24") (name "/CLK_B") (class "Default")
      (node (ref "LD2") (pin "3") (pinfunction "D_3") (pintype "input"))
      (node (ref "U2") (pin "58") (pinfunction "PB4_58") (pintype "bidirectional"))
    )
    (net (code "25") (name "/CLK_C") (class "Default")
      (node (ref "LD3") (pin "3") (pinfunction "D_3") (pintype "input"))
      (node (ref "U2") (pin "31") (pinfunction "PF3_31") (pintype "bidirectional"))
    )
    (net (code "26") (name "/DATA1_A") (class "Default")
      (node (ref "JEn1") (pin "2") (pinfunction "DATA1_2") (pintype "passive"))
      (node (ref "LD1") (pin "8") (pinfunction "A_8") (pintype "passive"))
    )
    (net (code "27") (name "/DATA1_B") (class "Default")
      (node (ref "JEn2") (pin "2") (pinfunction "DATA1_2") (pintype "passive"))
      (node (ref "LD2") (pin "8") (pinfunction "A_8") (pintype "passive"))
    )
    (net (code "28") (name "/DATA1_C") (class "Default")
      (node (ref "JEn3") (pin "2") (pinfunction "DATA1_2") (pintype "passive"))
      (node (ref "LD3") (pin "8") (pinfunction "A_8") (pintype "passive"))
    )
    (net (code "29") (name "/DATA2_A") (class "Default")
      (node (ref "JEn1") (pin "3") (pinfunction "DATA2_3") (pintype "passive"))
      (node (ref "LD1") (pin "7") (pinfunction "B_7") (pintype "passive"))
    )
    (net (code "30") (name "/DATA2_B") (class "Default")
      (node (ref "JEn2") (pin "3") (pinfunction "DATA2_3") (pintype "passive"))
      (node (ref "LD2") (pin "7") (pinfunction "B_7") (pintype "passive"))
    )
    (net (code "31") (name "/DATA2_C") (class "Default")
      (node (ref "JEn3") (pin "3") (pinfunction "DATA2_3") (pintype "passive"))
      (node (ref "LD3") (pin "7") (pinfunction "B_7") (pintype "passive"))
    )
    (net (code "32") (name "/DATA_A") (class "Default")
      (node (ref "LD1") (pin "2") (pinfunction "R_2") (pintype "output"))
      (node (ref "U2") (pin "22") (pinfunction "PA5/SSI0TX_22") (pintype "bidirectional"))
    )
    (net (code "33") (name "/DATA_B") (class "Default")
      (node (ref "LD2") (pin "2") (pinfunction "R_2") (pintype "output"))
      (node (ref "U2") (pin "57") (pinfunction "PB5_57") (pintype "bidirectional"))
    )
    (net (code "34") (name "/DATA_C") (class "Default")
      (node (ref "LD3") (pin "2") (pinfunction "R_2") (pintype "output"))
      (node (ref "U2") (pin "29") (pinfunction "PF1_29") (pintype "bidirectional"))
    )
    (net (code "35") (name "/DM") (class "Default")
      (node (ref "R8") (pin "1") (pinfunction "1_1") (pintype "passive"))
      (node (ref "USB1") (pin "2") (pinfunction "D-_2") (pintype "passive"))
    )
    (net (code "36") (name "/DP") (class "Default")
      (node (ref "R9") (pin "1") (pinfunction "1_1") (pintype "passive"))
      (node (ref "USB1") (pin "3") (pinfunction "D+_3") (pintype "passive"))
    )
    (net (code "37") (name "/H1M1") (class "Default")
      (node (ref "JH1") (pin "3") (pinfunction "3_3") (pintype "passive"))
      (node (ref "U2") (pin "16") (pinfunction "PC4_16") (pintype "bidirectional"))
    )
    (net (code "38") (name "/H1M2") (class "Default")
      (node (ref "JH2") (pin "3") (pinfunction "3_3") (pintype "passive"))
      (node (ref "U2") (pin "13") (pinfunction "PC7_13") (pintype "bidirectional"))
    )
    (net (code "39") (name "/H1M3") (class "Default")
      (node (ref "JH3") (pin "3") (pinfunction "3_3") (pintype "passive"))
      (node (ref "U2") (pin "63") (pinfunction "PD2_63") (pintype "bidirectional"))
    )
    (net (code "40") (name "/H2M1") (class "Default")
      (node (ref "JH1") (pin "2") (pinfunction "2_2") (pintype "passive"))
      (node (ref "U2") (pin "15") (pinfunction "PC5_15") (pintype "bidirectional"))
    )
    (net (code "41") (name "/H2M2") (class "Default")
      (node (ref "JH2") (pin "2") (pinfunction "2_2") (pintype "passive"))
      (node (ref "U2") (pin "61") (pinfunction "PD0_61") (pintype "bidirectional"))
    )
    (net (code "42") (name "/H2M3") (class "Default")
      (node (ref "JH3") (pin "2") (pinfunction "2_2") (pintype "passive"))
      (node (ref "U2") (pin "64") (pinfunction "PD3_64") (pintype "bidirectional"))
    )
    (net (code "43") (name "/H3M1") (class "Default")
      (node (ref "JH1") (pin "1") (pinfunction "1_1") (pintype "passive"))
      (node (ref "U2") (pin "14") (pinfunction "PC6_14") (pintype "bidirectional"))
    )
    (net (code "44") (name "/H3M2") (class "Default")
      (node (ref "JH2") (pin "1") (pinfunction "1_1") (pintype "passive"))
      (node (ref "U2") (pin "62") (pinfunction "PD1_62") (pintype "bidirectional"))
    )
    (net (code "45") (name "/H3M3") (class "Default")
      (node (ref "JH3") (pin "1") (pinfunction "1_1") (pintype "passive"))
      (node (ref "U2") (pin "43") (pinfunction "PD4_43") (pintype "bidirectional"))
    )
    (net (code "46") (name "/NO1") (class "Default")
      (node (ref "JLS") (pin "14") (pinfunction "14_14") (pintype "passive"))
      (node (ref "R15") (pin "1") (pinfunction "1_1") (pintype "passive"))
      (node (ref "U2") (pin "23") (pinfunction "PA6_23") (pintype "bidirectional"))
    )
    (net (code "47") (name "/NO2") (class "Default")
      (node (ref "JLS") (pin "13") (pinfunction "13_13") (pintype "passive"))
      (node (ref "R16") (pin "1") (pinfunction "1_1") (pintype "passive"))
      (node (ref "U2") (pin "24") (pinfunction "PA7_24") (pintype "bidirectional"))
    )
    (net (code "48") (name "/NO3") (class "Default")
      (node (ref "JLS") (pin "12") (pinfunction "12_12") (pintype "passive"))
      (node (ref "R17") (pin "1") (pinfunction "1_1") (pintype "passive"))
      (node (ref "U2") (pin "1") (pinfunction "PB6_1") (pintype "bidirectional"))
    )
    (net (code "49") (name "/NO4") (class "Default")
      (node (ref "JLS") (pin "11") (pinfunction "11_11") (pintype "passive"))
      (node (ref "R18") (pin "1") (pinfunction "1_1") (pintype "passive"))
      (node (ref "U2") (pin "4") (pinfunction "PB7_4") (pintype "bidirectional"))
    )
    (net (code "50") (name "/NO5") (class "Default")
      (node (ref "JLS") (pin "10") (pinfunction "10_10") (pintype "passive"))
      (node (ref "R19") (pin "1") (pinfunction "1_1") (pintype "passive"))
      (node (ref "U2") (pin "45") (pinfunction "PB0/USB0ID_45") (pintype "bidirectional"))
    )
    (net (code "51") (name "/NO6") (class "Default")
      (node (ref "JLS") (pin "9") (pinfunction "9_9") (pintype "passive"))
      (node (ref "R20") (pin "1") (pinfunction "1_1") (pintype "passive"))
      (node (ref "U2") (pin "46") (pinfunction "PB1/USB0VBUS_46") (pintype "bidirectional"))
    )
    (net (code "52") (name "/OSC0") (class "Default")
      (node (ref "C18") (pin "2") (pinfunction "2_2") (pintype "passive"))
      (node (ref "U2") (pin "40") (pinfunction "OSC0_40") (pintype "input"))
      (node (ref "X1") (pin "1") (pintype "passive"))
    )
    (net (code "53") (name "/OSC1") (class "Default")
      (node (ref "C19") (pin "2") (pinfunction "2_2") (pintype "passive"))
      (node (ref "U2") (pin "41") (pinfunction "OSC1_41") (pintype "output"))
      (node (ref "X1") (pin "3") (pintype "passive"))
    )
    (net (code "54") (name "/PWM1") (class "Default")
      (node (ref "JSC1") (pin "5") (pinfunction "5_5") (pintype "bidirectional"))
      (node (ref "U2") (pin "28") (pinfunction "PF0_28") (pintype "bidirectional"))
    )
    (net (code "55") (name "/PWM2") (class "Default")
      (node (ref "JSC2") (pin "5") (pinfunction "5_5") (pintype "bidirectional"))
      (node (ref "U2") (pin "20") (pinfunction "PA3/SSI0FSS_20") (pintype "bidirectional"))
    )
    (net (code "56") (name "/PWM3") (class "Default")
      (node (ref "JSC3") (pin "5") (pinfunction "5_5") (pintype "bidirectional"))
      (node (ref "U2") (pin "30") (pinfunction "PF2_30") (pintype "bidirectional"))
    )
    (net (code "57") (name "/RESET") (class "Default")
      (node (ref "C27") (pin "2") (pinfunction "2_2") (pintype "passive"))
      (node (ref "R3") (pin "2") (pinfunction "2_2") (pintype "passive"))
      (node (ref "U2") (pin "38") (pinfunction "RESET_38") (pintype "input"))
    )
    (net (code "58") (name "/SHIELD") (class "Default")
      (node (ref "C2") (pin "2") (pinfunction "2_2") (pintype "passive"))
      (node (ref "R1") (pin "2") (pinfunction "2_2") (pintype "passive"))
      (node (ref "USB1") (pin "5") (pinfunction "SHIELD_5") (pintype "passive"))
      (node (ref "USB1") (pin "6") (pinfunction "SHIELD_6") (pintype "passive"))
    )
    (net (code "59") (name "/SSRIn") (class "Default")
      (node (ref "SSR") (pin "1") (pinfunction "+CONTROL_1") (pintype "passive"))
      (node (ref "U2") (pin "48") (pinfunction "PB3/I2COSDA_48") (pintype "bidirectional"))
    )
    (net (code "60") (name "/SSRIn2") (class "Default")
      (node (ref "SSR2") (pin "1") (pinfunction "+CONTROL_1") (pintype "passive"))
      (node (ref "U2") (pin "47") (pinfunction "PB2/I2COSCL_47") (pintype "bidirectional"))
    )
    (net (code "61") (name "/SSROut") (class "Default")
      (node (ref "JBr1") (pin "1") (pinfunction "1_1") (pintype "passive"))
      (node (ref "SSR") (pin "3") (pinfunction "LOAD_1_3") (pintype "passive"))
    )
    (net (code "62") (name "/SSROut2") (class "Default")
      (node (ref "JBr2") (pin "1") (pinfunction "1_1") (pintype "passive"))
      (node (ref "SSR2") (pin "3") (pinfunction "LOAD_1_3") (pintype "passive"))
    )
    (net (code "63") (name "/TCK") (class "Default")
      (node (ref "P1") (pin "2") (pinfunction "2_2") (pintype "passive"))
      (node (ref "R2") (pin "2") (pinfunction "2_2") (pintype "passive"))
      (node (ref "U2") (pin "52") (pinfunction "PC0/TCK/SWCLK_52") (pintype "bidirectional"))
    )
    (net (code "64") (name "/TDI") (class "Default")
      (node (ref "P1") (pin "4") (pinfunction "4_4") (pintype "passive"))
      (node (ref "U2") (pin "50") (pinfunction "PC2/TDI_50") (pintype "bidirectional"))
    )
    (net (code "65") (name "/TDO") (class "Default")
      (node (ref "P1") (pin "3") (pinfunction "3_3") (pintype "passive"))
      (node (ref "U2") (pin "49") (pinfunction "PC3/TDO/SWO_49") (pintype "bidirectional"))
    )
    (net (code "66") (name "/TMS") (class "Default")
      (node (ref "P1") (pin "5") (pinfunction "5_5") (pintype "passive"))
      (node (ref "U2") (pin "51") (pinfunction "PC1/TMS/SWDIO_51") (pintype "bidirectional"))
    )
    (net (code "67") (name "/USB RX LED") (class "Default")
      (node (ref "D2") (pin "2") (pinfunction "K_2") (pintype "passive"))
      (node (ref "U3") (pin "5") (pinfunction "CBUS2_5") (pintype "passive"))
    )
    (net (code "68") (name "/USB TX LED") (class "Default")
      (node (ref "D1") (pin "2") (pinfunction "K_2") (pintype "passive"))
      (node (ref "U3") (pin "11") (pinfunction "CBUS1_11") (pintype "passive"))
    )
    (net (code "69") (name "/USB_RX") (class "Default")
      (node (ref "R4") (pin "1") (pinfunction "1_1") (pintype "passive"))
      (node (ref "U2") (pin "17") (pinfunction "PA0/U0RX_17") (pintype "bidirectional"))
      (node (ref "U3") (pin "15") (pinfunction "TXD_15") (pintype "passive"))
    )
    (net (code "70") (name "/USB_TX") (class "Default")
      (node (ref "R5") (pin "1") (pinfunction "1_1") (pintype "passive"))
      (node (ref "U2") (pin "18") (pinfunction "PA1/U0TX_18") (pintype "bidirectional"))
      (node (ref "U3") (pin "2") (pinfunction "RXD_2") (pintype "passive"))
    )
    (net (code "71") (name "/VCORE") (class "Default")
      (node (ref "C24") (pin "2") (pinfunction "2_2") (pintype "passive"))
      (node (ref "C25") (pin "2") (pinfunction "2_2") (pintype "passive"))
      (node (ref "C26") (pin "2") (pinfunction "2_2") (pintype "passive"))
      (node (ref "U2") (pin "25") (pinfunction "VDDC_25") (pintype "power_in"))
      (node (ref "U2") (pin "56") (pinfunction "VDDC_56") (pintype "power_in"))
    )
    (net (code "72") (name "GND") (class "Default")
      (node (ref "C1") (pin "2") (pinfunction "2_2") (pintype "passive"))
      (node (ref "C10") (pin "2") (pinfunction "2_2") (pintype "passive"))
      (node (ref "C11") (pin "2") (pinfunction "2_2") (pintype "passive"))
      (node (ref "C12") (pin "2") (pinfunction "2_2") (pintype "passive"))
      (node (ref "C13") (pin "1") (pinfunction "1_1") (pintype "passive"))
      (node (ref "C14") (pin "1") (pinfunction "1_1") (pintype "passive"))
      (node (ref "C15") (pin "1") (pinfunction "1_1") (pintype "passive"))
      (node (ref "C16") (pin "1") (pinfunction "1_1") (pintype "passive"))
      (node (ref "C17") (pin "1") (pinfunction "1_1") (pintype "passive"))
      (node (ref "C18") (pin "1") (pinfunction "1_1") (pintype "passive"))
      (node (ref "C19") (pin "1") (pinfunction "1_1") (pintype "passive"))
      (node (ref "C2") (pin "1") (pinfunction "1_1") (pintype "passive"))
      (node (ref "C20") (pin "1") (pinfunction "1_1") (pintype "passive"))
      (node (ref "C21") (pin "1") (pinfunction "1_1") (pintype "passive"))
      (node (ref "C22") (pin "1") (pinfunction "1_1") (pintype "passive"))
      (node (ref "C23") (pin "1") (pinfunction "1_1") (pintype "passive"))
      (node (ref "C24") (pin "1") (pinfunction "1_1") (pintype "passive"))
      (node (ref "C25") (pin "1") (pinfunction "1_1") (pintype "passive"))
      (node (ref "C26") (pin "1") (pinfunction "1_1") (pintype "passive"))
      (node (ref "C27") (pin "1") (pinfunction "1_1") (pintype "passive"))
      (node (ref "C28") (pin "1") (pinfunction "1_1") (pintype "passive"))
      (node (ref "C29") (pin "1") (pinfunction "1_1") (pintype "passive"))
      (node (ref "C3") (pin "1") (pinfunction "1_1") (pintype "passive"))
      (node (ref "C4") (pin "1") (pinfunction "1_1") (pintype "passive"))
      (node (ref "C5") (pin "1") (pinfunction "1_1") (pintype "passive"))
      (node (ref "C6") (pin "1") (pinfunction "1_1") (pintype "passive"))
      (node (ref "C7") (pin "2") (pinfunction "2_2") (pintype "passive"))
      (node (ref "C8") (pin "2") (pinfunction "2_2") (pintype "passive"))
      (node (ref "C9") (pin "1") (pinfunction "1_1") (pintype "passive"))
      (node (ref "JBP") (pin "3") (pinfunction "3_3") (pintype "passive"))
      (node (ref "JBP") (pin "4") (pinfunction "4_4") (pintype "passive"))
      (node (ref "JBr1") (pin "2") (pinfunction "2_2") (pintype "passive"))
      (node (ref "JBr2") (pin "2") (pinfunction "2_2") (pintype "passive"))
      (node (ref "JEn1") (pin "6") (pinfunction "GND_6") (pintype "passive"))
      (node (ref "JEn2") (pin "6") (pinfunction "GND_6") (pintype "passive"))
      (node (ref "JEn3") (pin "6") (pinfunction "GND_6") (pintype "passive"))
      (node (ref "JH1") (pin "4") (pinfunction "4_4") (pintype "passive"))
      (node (ref "JH2") (pin "4") (pinfunction "4_4") (pintype "passive"))
      (node (ref "JH3") (pin "4") (pinfunction "4_4") (pintype "passive"))
      (node (ref "JLS") (pin "3") (pinfunction "3_3") (pintype "passive"))
      (node (ref "JLS") (pin "4") (pinfunction "4_4") (pintype "passive"))
      (node (ref "JLS") (pin "5") (pinfunction "5_5") (pintype "passive"))
      (node (ref "JLS") (pin "6") (pinfunction "6_6") (pintype "passive"))
      (node (ref "JLS") (pin "7") (pinfunction "7_7") (pintype "passive"))
      (node (ref "JLS") (pin "8") (pinfunction "8_8") (pintype "passive"))
      (node (ref "JSC1") (pin "7") (pinfunction "7_7") (pintype "bidirectional"))
      (node (ref "JSC2") (pin "7") (pinfunction "7_7") (pintype "bidirectional"))
      (node (ref "JSC3") (pin "7") (pinfunction "7_7") (pintype "bidirectional"))
      (node (ref "LD1") (pin "4") (pinfunction "GND_4") (pintype "power_in"))
      (node (ref "LD2") (pin "4") (pinfunction "GND_4") (pintype "power_in"))
      (node (ref "LD3") (pin "4") (pinfunction "GND_4") (pintype "power_in"))
      (node (ref "P1") (pin "1") (pinfunction "1_1") (pintype "passive"))
      (node (ref "R1") (pin "1") (pinfunction "1_1") (pintype "passive"))
      (node (ref "SSR") (pin "2") (pinfunction "-CONTROL_2") (pintype "passive"))
      (node (ref "SSR2") (pin "2") (pinfunction "-CONTROL_2") (pintype "passive"))
      (node (ref "U1") (pin "2") (pinfunction "GND_2") (pintype "power_in"))
      (node (ref "U1") (pin "4") (pinfunction "GND_4") (pintype "power_in"))
      (node (ref "U2") (pin "12") (pinfunction "GND_12") (pintype "power_in"))
      (node (ref "U2") (pin "27") (pinfunction "GND_27") (pintype "power_in"))
      (node (ref "U2") (pin "3") (pinfunction "GNDA_3") (pintype "power_in"))
      (node (ref "U2") (pin "32") (pinfunction "WAKE_32") (pintype "input"))
      (node (ref "U2") (pin "34") (pinfunction "XOSC0_34") (pintype "input"))
      (node (ref "U2") (pin "35") (pinfunction "GNDX_35") (pintype "power_in"))
      (node (ref "U2") (pin "39") (pinfunction "GND_39") (pintype "power_in"))
      (node (ref "U2") (pin "55") (pinfunction "GND_55") (pintype "power_in"))
      (node (ref "U3") (pin "13") (pinfunction "GND_13") (pintype "passive"))
      (node (ref "U3") (pin "17") (pinfunction "GND_17") (pintype "passive"))
      (node (ref "U3") (pin "3") (pinfunction "GND_3") (pintype "passive"))
      (node (ref "USB1") (pin "4") (pinfunction "GND_4") (pintype "power_in"))
      (node (ref "X1") (pin "2") (pinfunction "CASE_2") (pintype "passive"))
      (node (ref "X1") (pin "4") (pinfunction "CASE_4") (pintype "passive"))
    )
    (net (code "73") (name "Net-(D1-A)") (class "Default")
      (node (ref "D1") (pin "1") (pinfunction "A_1") (pintype "passive"))
      (node (ref "R13") (pin "1") (pinfunction "1_1") (pintype "passive"))
    )
    (net (code "74") (name "Net-(D2-A)") (class "Default")
      (node (ref "D2") (pin "1") (pinfunction "A_1") (pintype "passive"))
      (node (ref "R14") (pin "1") (pinfunction "1_1") (pintype "passive"))
    )
    (net (code "75") (name "Net-(U3-CTS#)") (class "Default")
      (node (ref "R7") (pin "1") (pinfunction "1_1") (pintype "passive"))
      (node (ref "U3") (pin "4") (pinfunction "CTS#_4") (pintype "passive"))
    )
    (net (code "76") (name "Net-(U3-RTS#)") (class "Default")
      (node (ref "R6") (pin "1") (pinfunction "1_1") (pintype "passive"))
      (node (ref "U3") (pin "16") (pinfunction "RTS#_16") (pintype "passive"))
    )
    (net (code "77") (name "Net-(U3-USBDM)") (class "Default")
      (node (ref "R8") (pin "2") (pinfunction "2_2") (pintype "passive"))
      (node (ref "U3") (pin "7") (pinfunction "USBDM_7") (pintype "passive"))
    )
    (net (code "78") (name "Net-(U3-USBDP)") (class "Default")
      (node (ref "R9") (pin "2") (pinfunction "2_2") (pintype "passive"))
      (node (ref "U3") (pin "6") (pinfunction "USBDP_6") (pintype "passive"))
    )
    (net (code "79") (name "VBUS") (class "Default")
      (node (ref "C1") (pin "1") (pinfunction "1_1") (pintype "passive"))
      (node (ref "C3") (pin "2") (pinfunction "2_2") (pintype "passive"))
      (node (ref "L1") (pin "1") (pinfunction "1_1") (pintype "passive"))
      (node (ref "USB1") (pin "1") (pinfunction "VDD_1") (pintype "power_in"))
    )
    (net (code "80") (name "unconnected-(JBP-PadMH1)") (class "Default")
      (node (ref "JBP") (pin "MH1") (pinfunction "MH1_MH1") (pintype "passive"))
    )
    (net (code "81") (name "unconnected-(JBP-PadMH2)") (class "Default")
      (node (ref "JBP") (pin "MH2") (pinfunction "MH2_MH2") (pintype "passive"))
    )
    (net (code "82") (name "unconnected-(JH1-Pad6)") (class "Default")
      (node (ref "JH1") (pin "6") (pinfunction "6_6") (pintype "passive"))
    )
    (net (code "83") (name "unconnected-(JH2-Pad6)") (class "Default")
      (node (ref "JH2") (pin "6") (pinfunction "6_6") (pintype "passive"))
    )
    (net (code "84") (name "unconnected-(JH3-Pad6)") (class "Default")
      (node (ref "JH3") (pin "6") (pinfunction "6_6") (pintype "passive"))
    )
    (net (code "85") (name "unconnected-(JLS-Pad1)") (class "Default")
      (node (ref "JLS") (pin "1") (pinfunction "1_1") (pintype "passive"))
    )
    (net (code "86") (name "unconnected-(JLS-Pad2)") (class "Default")
      (node (ref "JLS") (pin "2") (pinfunction "2_2") (pintype "passive"))
    )
    (net (code "87") (name "unconnected-(JSC1-Pad8)") (class "Default")
      (node (ref "JSC1") (pin "8") (pinfunction "8_8") (pintype "bidirectional"))
    )
    (net (code "88") (name "unconnected-(JSC2-Pad8)") (class "Default")
      (node (ref "JSC2") (pin "8") (pinfunction "8_8") (pintype "bidirectional"))
    )
    (net (code "89") (name "unconnected-(JSC3-Pad8)") (class "Default")
      (node (ref "JSC3") (pin "8") (pinfunction "8_8") (pintype "bidirectional"))
    )
    (net (code "90") (name "unconnected-(U2-HIB-Pad33)") (class "Default")
      (node (ref "U2") (pin "33") (pinfunction "HIB_33") (pintype "output+no_connect"))
    )
    (net (code "91") (name "unconnected-(U2-PA4{slash}SSI0RX-Pad21)") (class "Default")
      (node (ref "U2") (pin "21") (pinfunction "PA4/SSI0RX_21") (pintype "bidirectional"))
    )
    (net (code "92") (name "unconnected-(U2-PF4-Pad5)") (class "Default")
      (node (ref "U2") (pin "5") (pinfunction "PF4_5") (pintype "bidirectional"))
    )
    (net (code "93") (name "unconnected-(U2-XOSC1-Pad36)") (class "Default")
      (node (ref "U2") (pin "36") (pinfunction "XOSC1_36") (pintype "output+no_connect"))
    )
    (net (code "94") (name "unconnected-(U3-CBUS0-Pad12)") (class "Default")
      (node (ref "U3") (pin "12") (pinfunction "CBUS0_12") (pintype "passive+no_connect"))
    )
    (net (code "95") (name "unconnected-(U3-CBUS3-Pad14)") (class "Default")
      (node (ref "U3") (pin "14") (pinfunction "CBUS3_14") (pintype "passive+no_connect"))
    )
  )
)
